# diff_curr_to_S_E_volt_with_LP_filter.net
KiCad netlist of a schematic drawn in Altium Designer
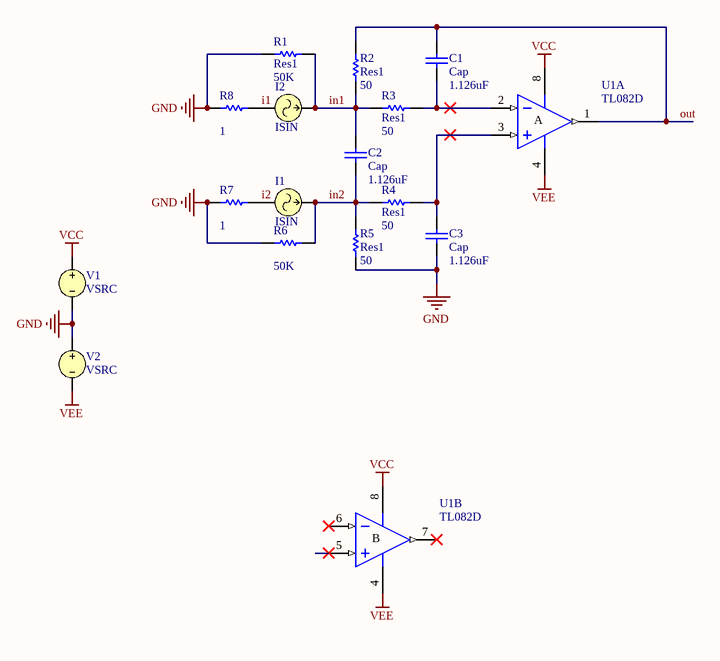
[diagram p0: diff_curr_to_S_E_volt_with_LP_filter.SchDoc]

(export (version "E")
  (design (tool "Eeschema 10.0.6"))
  (components
    (comp (ref "C1")
      (value "Cap")
      (footprint "RAD-0.3")
      (description "Capacitor")
      (fields (field (name "ALTIUM_VALUE") "1.126uF") (field (name "PUBLISHER") "Altium Limited"))
      (libsource (lib "Miscellaneous Devices") (part "Cap"))
    )
    (comp (ref "C2")
      (value "Cap")
      (footprint "RAD-0.3")
      (description "Capacitor")
      (fields (field (name "ALTIUM_VALUE") "1.126uF") (field (name "PUBLISHER") "Altium Limited"))
      (libsource (lib "Miscellaneous Devices") (part "Cap"))
    )
    (comp (ref "C3")
      (value "Cap")
      (footprint "RAD-0.3")
      (description "Capacitor")
      (fields (field (name "ALTIUM_VALUE") "1.126uF") (field (name "PUBLISHER") "Altium Limited"))
      (libsource (lib "Miscellaneous Devices") (part "Cap"))
    )
    (comp (ref "I1")
      (value "ISIN")
      (description "Sinusoidal Current Source")
      (fields (field (name "PUBLISHER") "Altium Limited"))
      (libsource (lib "Simulation Sources") (part "ISIN"))
    )
    (comp (ref "I2")
      (value "ISIN")
      (description "Sinusoidal Current Source")
      (fields (field (name "PUBLISHER") "Altium Limited"))
      (libsource (lib "Simulation Sources") (part "ISIN"))
    )
    (comp (ref "R1")
      (value "Res1")
      (footprint "AXIAL-0.3")
      (description "Resistor")
      (fields (field (name "ALTIUM_VALUE") "50K") (field (name "PUBLISHER") "Altium Limited"))
      (libsource (lib "Miscellaneous Devices") (part "Res1"))
    )
    (comp (ref "R2")
      (value "Res1")
      (footprint "AXIAL-0.3")
      (description "Resistor")
      (fields (field (name "ALTIUM_VALUE") "50") (field (name "PUBLISHER") "Altium Limited"))
      (libsource (lib "Miscellaneous Devices") (part "Res1"))
    )
    (comp (ref "R3")
      (value "Res1")
      (footprint "AXIAL-0.3")
      (description "Resistor")
      (fields (field (name "ALTIUM_VALUE") "50") (field (name "PUBLISHER") "Altium Limited"))
      (libsource (lib "Miscellaneous Devices") (part "Res1"))
    )
    (comp (ref "R4")
      (value "Res1")
      (footprint "AXIAL-0.3")
      (description "Resistor")
      (fields (field (name "ALTIUM_VALUE") "50") (field (name "PUBLISHER") "Altium Limited"))
      (libsource (lib "Miscellaneous Devices") (part "Res1"))
    )
    (comp (ref "R5")
      (value "Res1")
      (footprint "AXIAL-0.3")
      (description "Resistor")
      (fields (field (name "ALTIUM_VALUE") "50") (field (name "PUBLISHER") "Altium Limited"))
      (libsource (lib "Miscellaneous Devices") (part "Res1"))
    )
    (comp (ref "R6")
      (value "50K")
      (footprint "AXIAL-0.3")
      (description "Resistor")
      (fields (field (name "Comment") "Res1") (field (name "PUBLISHER") "Altium Limited"))
      (libsource (lib "Miscellaneous Devices") (part "Res1"))
    )
    (comp (ref "R7")
      (value "1")
      (footprint "AXIAL-0.3")
      (description "Resistor")
      (fields (field (name "Comment") "Res1") (field (name "PUBLISHER") "Altium Limited"))
      (libsource (lib "Miscellaneous Devices") (part "Res1"))
    )
    (comp (ref "R8")
      (value "1")
      (footprint "AXIAL-0.3")
      (description "Resistor")
      (fields (field (name "Comment") "Res1") (field (name "PUBLISHER") "Altium Limited"))
      (libsource (lib "Miscellaneous Devices") (part "Res1"))
    )
    (comp (ref "U1")
      (value "TL082D")
      (footprint "D008_L")
      (description "JFET-Input Operational Amplifier")
      (fields (field (name "PUBLISHER") "Altium Limited"))
      (libsource (lib "TI Operational Amplifier") (part "TL082D"))
    )
    (comp (ref "V1")
      (value "VSRC")
      (description "Voltage Source")
      (fields (field (name "PUBLISHER") "Altium Limited"))
      (libsource (lib "Simulation Sources") (part "VSRC"))
    )
    (comp (ref "V2")
      (value "VSRC")
      (description "Voltage Source")
      (fields (field (name "PUBLISHER") "Altium Limited"))
      (libsource (lib "Simulation Sources") (part "VSRC"))
    )
  )
  (nets
    (net (code "1") (name "/i1") (class "Default")
      (node (ref "I2") (pin "1") (pinfunction "1_1") (pintype "passive"))
      (node (ref "R8") (pin "1") (pinfunction "1_1") (pintype "passive"))
    )
    (net (code "2") (name "/i2") (class "Default")
      (node (ref "I1") (pin "1") (pinfunction "1_1") (pintype "passive"))
      (node (ref "R7") (pin "1") (pinfunction "1_1") (pintype "passive"))
    )
    (net (code "3") (name "/in1") (class "Default")
      (node (ref "C2") (pin "1") (pinfunction "1_1") (pintype "passive"))
      (node (ref "I2") (pin "2") (pinfunction "2_2") (pintype "passive"))
      (node (ref "R1") (pin "1") (pinfunction "1_1") (pintype "passive"))
      (node (ref "R2") (pin "1") (pinfunction "1_1") (pintype "passive"))
      (node (ref "R3") (pin "1") (pinfunction "1_1") (pintype "passive"))
    )
    (net (code "4") (name "/in2") (class "Default")
      (node (ref "C2") (pin "2") (pinfunction "2_2") (pintype "passive"))
      (node (ref "I1") (pin "2") (pinfunction "2_2") (pintype "passive"))
      (node (ref "R4") (pin "1") (pinfunction "1_1") (pintype "passive"))
      (node (ref "R5") (pin "2") (pinfunction "2_2") (pintype "passive"))
      (node (ref "R6") (pin "1") (pinfunction "1_1") (pintype "passive"))
    )
    (net (code "5") (name "/out") (class "Default")
      (node (ref "C1") (pin "2") (pinfunction "2_2") (pintype "passive"))
      (node (ref "R2") (pin "2") (pinfunction "2_2") (pintype "passive"))
      (node (ref "U1") (pin "1") (pinfunction "OUT_1") (pintype "output"))
    )
    (net (code "6") (name "GND") (class "Default")
      (node (ref "C3") (pin "1") (pinfunction "1_1") (pintype "passive"))
      (node (ref "R1") (pin "2") (pinfunction "2_2") (pintype "passive"))
      (node (ref "R5") (pin "1") (pinfunction "1_1") (pintype "passive"))
      (node (ref "R6") (pin "2") (pinfunction "2_2") (pintype "passive"))
      (node (ref "R7") (pin "2") (pinfunction "2_2") (pintype "passive"))
      (node (ref "R8") (pin "2") (pinfunction "2_2") (pintype "passive"))
      (node (ref "V1") (pin "2") (pinfunction "2_2") (pintype "passive"))
      (node (ref "V2") (pin "1") (pinfunction "1_1") (pintype "passive"))
    )
    (net (code "7") (name "Net-(U1A-IN+)") (class "Default")
      (node (ref "C3") (pin "2") (pinfunction "2_2") (pintype "passive"))
      (node (ref "R4") (pin "2") (pinfunction "2_2") (pintype "passive"))
      (node (ref "U1") (pin "3") (pinfunction "IN+_3") (pintype "input"))
    )
    (net (code "8") (name "Net-(U1A-IN-)") (class "Default")
      (node (ref "C1") (pin "1") (pinfunction "1_1") (pintype "passive"))
      (node (ref "R3") (pin "2") (pinfunction "2_2") (pintype "passive"))
      (node (ref "U1") (pin "2") (pinfunction "IN-_2") (pintype "input"))
    )
    (net (code "9") (name "VCC") (class "Default")
      (node (ref "U1") (pin "8") (pinfunction "V+_8") (pintype "power_in"))
      (node (ref "V1") (pin "1") (pinfunction "1_1") (pintype "passive"))
    )
    (net (code "10") (name "VEE") (class "Default")
      (node (ref "U1") (pin "4") (pinfunction "V-_4") (pintype "power_in"))
      (node (ref "V2") (pin "2") (pinfunction "2_2") (pintype "passive"))
    )
    (net (code "11") (name "unconnected-(U1B-IN+-Pad5)") (class "Default")
      (node (ref "U1") (pin "5") (pinfunction "IN+_5") (pintype "input+no_connect"))
    )
    (net (code "12") (name "unconnected-(U1B-IN--Pad6)") (class "Default")
      (node (ref "U1") (pin "6") (pinfunction "IN-_6") (pintype "input+no_connect"))
    )
    (net (code "13") (name "unconnected-(U1B-OUT-Pad7)") (class "Default")
      (node (ref "U1") (pin "7") (pinfunction "OUT_7") (pintype "output+no_connect"))
    )
  )
)
